# UWB_Tag.net
KiCad netlist of a schematic drawn in Altium Designer
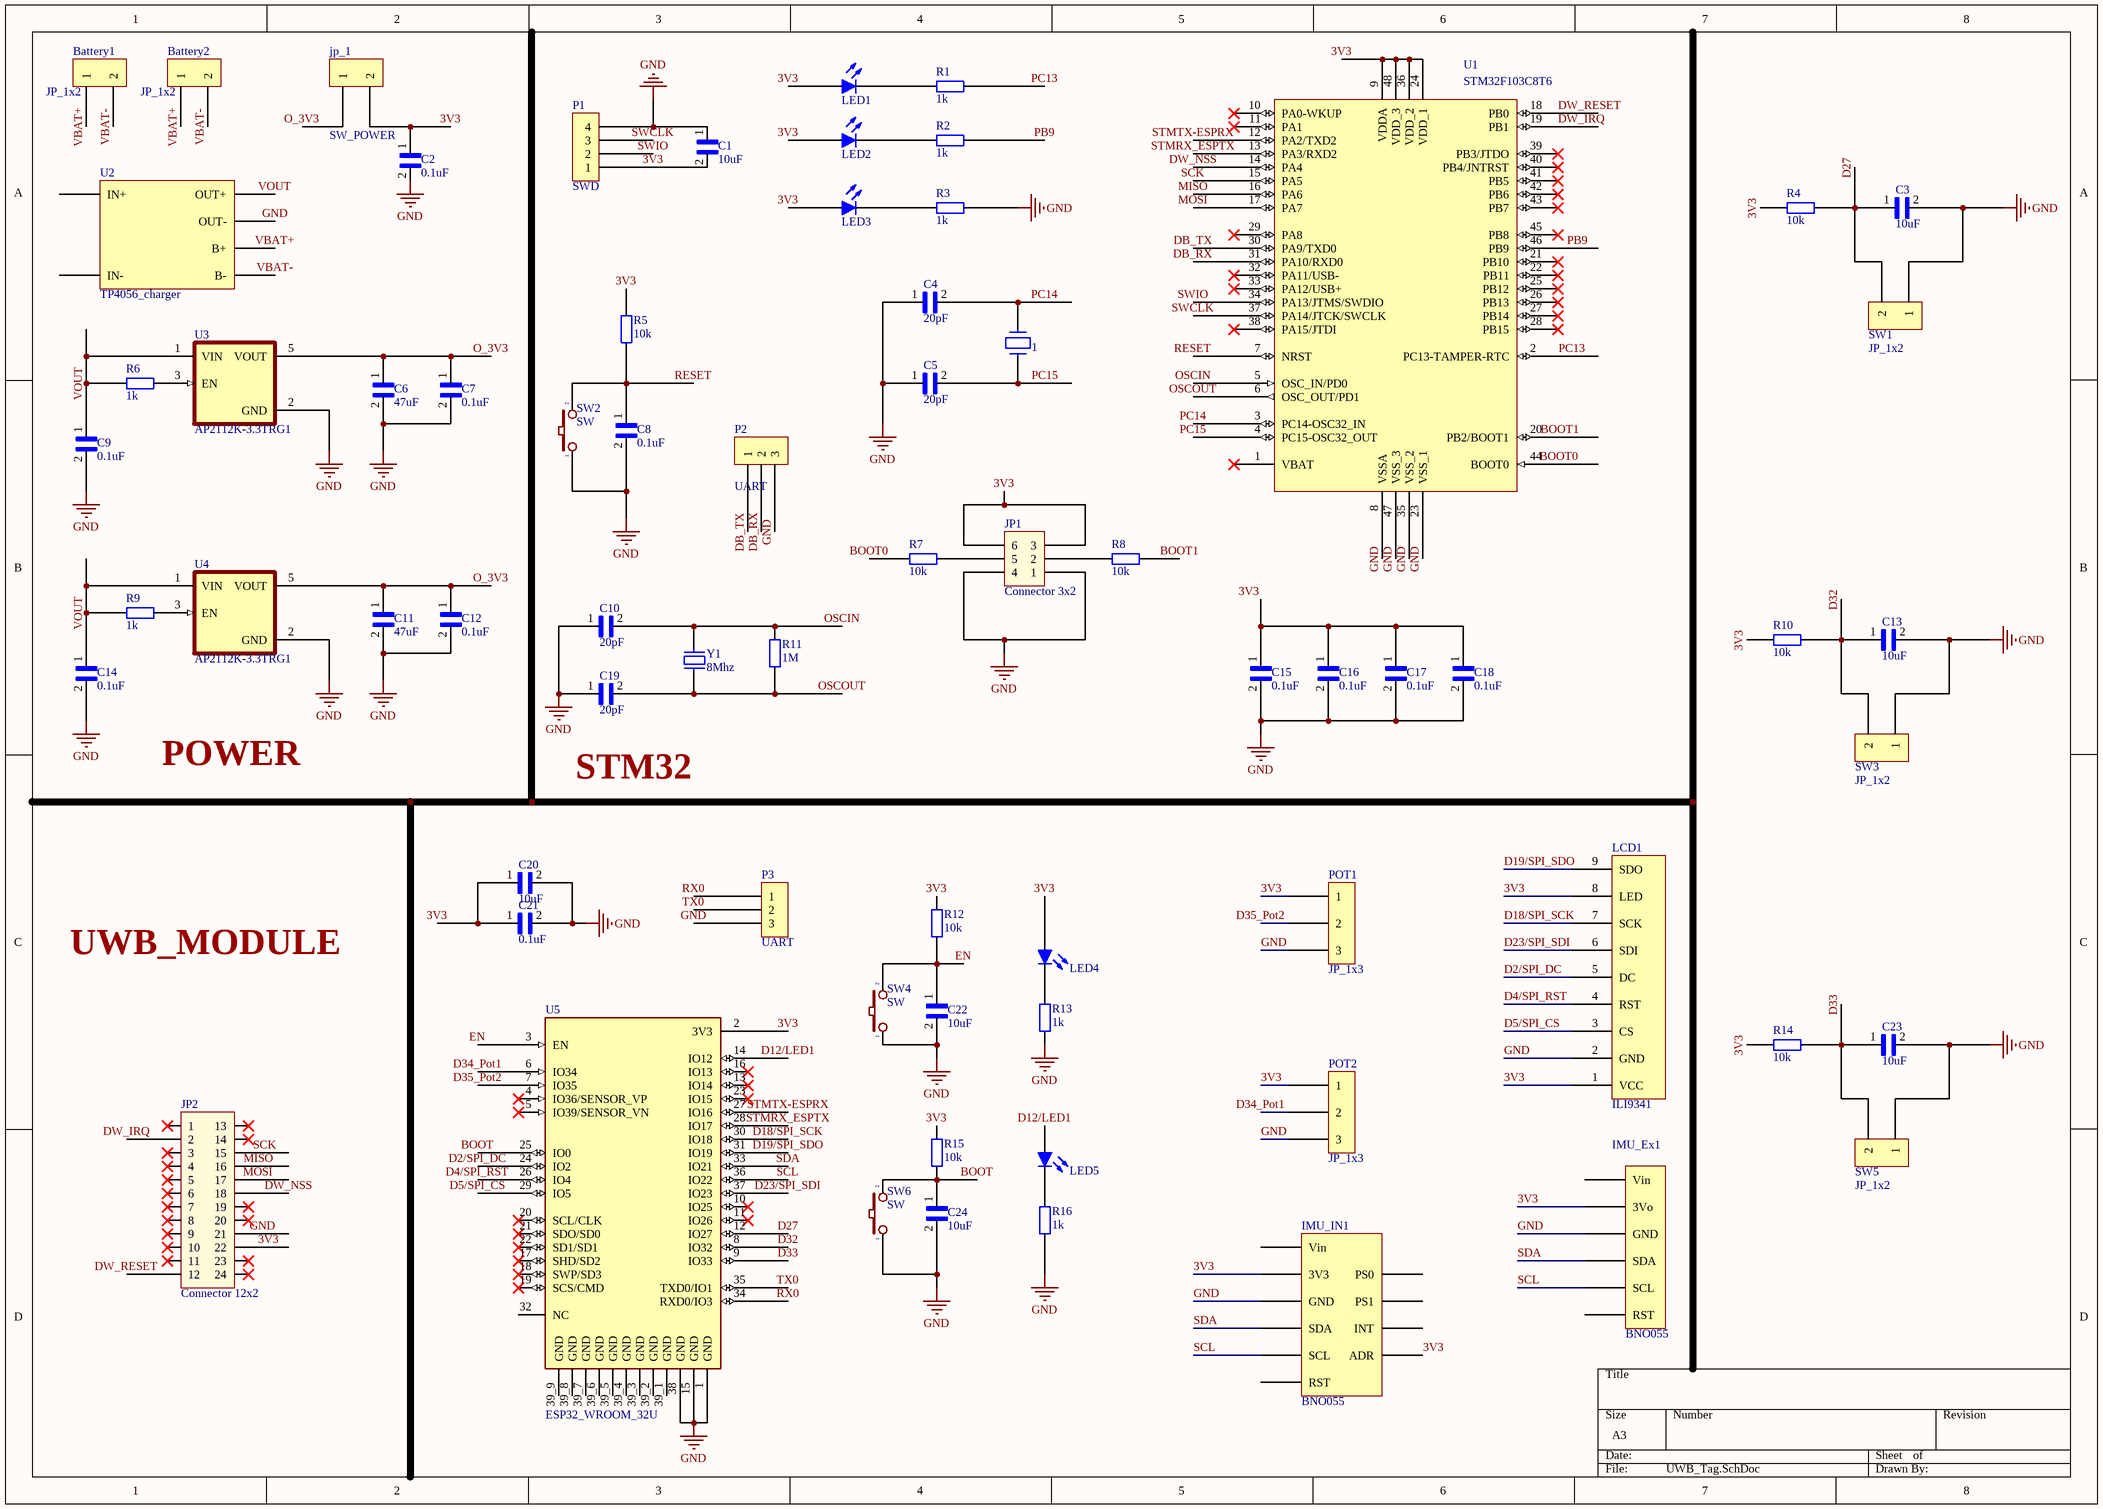
[diagram p0: UWB_Tag.SchDoc]

(export (version "E")
  (design (tool "Eeschema 10.0.6"))
  (components
    (comp (ref "1")
      (value "ABS07")
      (footprint "ABS07")
      (description "SMD Quartz Crystal")
      (fields (field (name "CREATED BY") "Zion Blue") (field (name "PUBLISHER") "Cynetik Group"))
      (libsource (lib "Cty1") (part "ABS07"))
    )
    (comp (ref "Battery1") (value "JP_1x2") (footprint "JP_1x2") (libsource (lib "") (part "JP_1x2_1")))
    (comp (ref "Battery2") (value "JP_1x2") (footprint "JP_1x2") (libsource (lib "") (part "JP_1x2_1")))
    (comp (ref "C1")
      (value "10uF")
      (footprint "Capacitor_0805")
      (description "Capacitor; Ceramic; Cap; .220uF; Tol 10%; SMT; Vol-Rtg 50V; X7R; Tape And Reel")
      (libsource (lib "") (part "Capacitor_0805_1"))
    )
    (comp (ref "C2")
      (value "0.1uF")
      (footprint "Capacitor_0805")
      (description "Capacitor; Ceramic; Cap; .220uF; Tol 10%; SMT; Vol-Rtg 50V; X7R; Tape And Reel")
      (libsource (lib "") (part "Capacitor_0805_1"))
    )
    (comp (ref "C3")
      (value "10uF")
      (footprint "Capacitor_0805")
      (description "Capacitor; Ceramic; Cap; .220uF; Tol 10%; SMT; Vol-Rtg 50V; X7R; Tape And Reel")
      (libsource (lib "Target_tracking_20242v3") (part "Capacitor_0805"))
    )
    (comp (ref "C4")
      (value "20pF")
      (footprint "Capacitor_0805")
      (description "Capacitor; Ceramic; Cap; .220uF; Tol 10%; SMT; Vol-Rtg 50V; X7R; Tape And Reel")
      (libsource (lib "Target_tracking_20242v3") (part "Capacitor_0805"))
    )
    (comp (ref "C5")
      (value "20pF")
      (footprint "Capacitor_0805")
      (description "Capacitor; Ceramic; Cap; .220uF; Tol 10%; SMT; Vol-Rtg 50V; X7R; Tape And Reel")
      (libsource (lib "Target_tracking_20242v3") (part "Capacitor_0805"))
    )
    (comp (ref "C6")
      (value "47uF")
      (footprint "Capacitor_0805")
      (description "Capacitor; Ceramic; Cap; .220uF; Tol 10%; SMT; Vol-Rtg 50V; X7R; Tape And Reel")
      (libsource (lib "") (part "Capacitor_0805_1"))
    )
    (comp (ref "C7")
      (value "0.1uF")
      (footprint "Capacitor_0805")
      (description "Capacitor; Ceramic; Cap; .220uF; Tol 10%; SMT; Vol-Rtg 50V; X7R; Tape And Reel")
      (libsource (lib "") (part "Capacitor_0805_1"))
    )
    (comp (ref "C8")
      (value "0.1uF")
      (footprint "Capacitor_0805")
      (description "Capacitor; Ceramic; Cap; .220uF; Tol 10%; SMT; Vol-Rtg 50V; X7R; Tape And Reel")
      (libsource (lib "") (part "Capacitor_0805_1"))
    )
    (comp (ref "C9")
      (value "0.1uF")
      (footprint "Capacitor_0805")
      (description "Capacitor; Ceramic; Cap; .220uF; Tol 10%; SMT; Vol-Rtg 50V; X7R; Tape And Reel")
      (libsource (lib "") (part "Capacitor_0805_1"))
    )
    (comp (ref "C10")
      (value "20pF")
      (footprint "Capacitor_0805")
      (description "Capacitor; Ceramic; Cap; .220uF; Tol 10%; SMT; Vol-Rtg 50V; X7R; Tape And Reel")
      (libsource (lib "Target_tracking_20242v3") (part "Capacitor_0805"))
    )
    (comp (ref "C11")
      (value "47uF")
      (footprint "Capacitor_0805")
      (description "Capacitor; Ceramic; Cap; .220uF; Tol 10%; SMT; Vol-Rtg 50V; X7R; Tape And Reel")
      (libsource (lib "") (part "Capacitor_0805_1"))
    )
    (comp (ref "C12")
      (value "0.1uF")
      (footprint "Capacitor_0805")
      (description "Capacitor; Ceramic; Cap; .220uF; Tol 10%; SMT; Vol-Rtg 50V; X7R; Tape And Reel")
      (libsource (lib "") (part "Capacitor_0805_1"))
    )
    (comp (ref "C13")
      (value "10uF")
      (footprint "Capacitor_0805")
      (description "Capacitor; Ceramic; Cap; .220uF; Tol 10%; SMT; Vol-Rtg 50V; X7R; Tape And Reel")
      (libsource (lib "Target_tracking_20242v3") (part "Capacitor_0805"))
    )
    (comp (ref "C14")
      (value "0.1uF")
      (footprint "Capacitor_0805")
      (description "Capacitor; Ceramic; Cap; .220uF; Tol 10%; SMT; Vol-Rtg 50V; X7R; Tape And Reel")
      (libsource (lib "") (part "Capacitor_0805_1"))
    )
    (comp (ref "C15")
      (value "0.1uF")
      (footprint "Capacitor_0805")
      (description "Capacitor; Ceramic; Cap; .220uF; Tol 10%; SMT; Vol-Rtg 50V; X7R; Tape And Reel")
      (libsource (lib "") (part "Capacitor_0805_1"))
    )
    (comp (ref "C16")
      (value "0.1uF")
      (footprint "Capacitor_0805")
      (description "Capacitor; Ceramic; Cap; .220uF; Tol 10%; SMT; Vol-Rtg 50V; X7R; Tape And Reel")
      (libsource (lib "") (part "Capacitor_0805_1"))
    )
    (comp (ref "C17")
      (value "0.1uF")
      (footprint "Capacitor_0805")
      (description "Capacitor; Ceramic; Cap; .220uF; Tol 10%; SMT; Vol-Rtg 50V; X7R; Tape And Reel")
      (libsource (lib "") (part "Capacitor_0805_1"))
    )
    (comp (ref "C18")
      (value "0.1uF")
      (footprint "Capacitor_0805")
      (description "Capacitor; Ceramic; Cap; .220uF; Tol 10%; SMT; Vol-Rtg 50V; X7R; Tape And Reel")
      (libsource (lib "") (part "Capacitor_0805_1"))
    )
    (comp (ref "C19")
      (value "20pF")
      (footprint "Capacitor_0805")
      (description "Capacitor; Ceramic; Cap; .220uF; Tol 10%; SMT; Vol-Rtg 50V; X7R; Tape And Reel")
      (libsource (lib "Target_tracking_20242v3") (part "Capacitor_0805"))
    )
    (comp (ref "C20")
      (value "10uF")
      (footprint "Capacitor_0805")
      (description "Capacitor; Ceramic; Cap; .220uF; Tol 10%; SMT; Vol-Rtg 50V; X7R; Tape And Reel")
      (libsource (lib "Target_tracking_20242v3") (part "Capacitor_0805"))
    )
    (comp (ref "C21")
      (value "0.1uF")
      (footprint "Capacitor_0805")
      (description "Capacitor; Ceramic; Cap; .220uF; Tol 10%; SMT; Vol-Rtg 50V; X7R; Tape And Reel")
      (libsource (lib "Target_tracking_20242v3") (part "Capacitor_0805"))
    )
    (comp (ref "C22")
      (value "10uF")
      (footprint "Capacitor_0805")
      (description "Capacitor; Ceramic; Cap; .220uF; Tol 10%; SMT; Vol-Rtg 50V; X7R; Tape And Reel")
      (libsource (lib "") (part "Capacitor_0805_1"))
    )
    (comp (ref "C23")
      (value "10uF")
      (footprint "Capacitor_0805")
      (description "Capacitor; Ceramic; Cap; .220uF; Tol 10%; SMT; Vol-Rtg 50V; X7R; Tape And Reel")
      (libsource (lib "Target_tracking_20242v3") (part "Capacitor_0805"))
    )
    (comp (ref "C24")
      (value "10uF")
      (footprint "Capacitor_0805")
      (description "Capacitor; Ceramic; Cap; .220uF; Tol 10%; SMT; Vol-Rtg 50V; X7R; Tape And Reel")
      (libsource (lib "") (part "Capacitor_0805_1"))
    )
    (comp (ref "IMU_Ex1")
      (value "BNO055")
      (footprint "BNO055_External")
      (libsource (lib "Target_tracking_20242v2") (part "BNO055_External"))
    )
    (comp (ref "IMU_IN1")
      (value "BNO055")
      (footprint "BNO055_Internal")
      (libsource (lib "Target_tracking_20242v3") (part "BNO055"))
    )
    (comp (ref "JP1") (value "Connector 3x2") (footprint "JP3x2") (libsource (lib "Cty1") (part "JP3x2")))
    (comp (ref "JP2")
      (value "Connector 12x2")
      (footprint "JP12X2_1")
      (libsource (lib "Cty1") (part "JP12x2"))
    )
    (comp (ref "jp_1")
      (value "SW_POWER")
      (footprint "JP_1x2")
      (libsource (lib "Target_tracking_20242v3") (part "JP_1x2"))
    )
    (comp (ref "LCD1")
      (value "ILI9341")
      (footprint "ILI9341_LCD3.5")
      (libsource (lib "Target_tracking_20242v2") (part "ILI9341_LCD3.5"))
    )
    (comp (ref "LED1")
      (value "Led")
      (footprint "Led 0805 Blue")
      (description "Typical LED")
      (libsource (lib "Project_LoRa") (part "Led"))
    )
    (comp (ref "LED2")
      (value "Led")
      (footprint "Led 0805 Blue")
      (description "Typical LED")
      (libsource (lib "Project_LoRa") (part "Led"))
    )
    (comp (ref "LED3")
      (value "Led")
      (footprint "Led 0805 Blue")
      (description "Typical LED")
      (libsource (lib "Project_LoRa") (part "Led"))
    )
    (comp (ref "LED4")
      (value "Led")
      (footprint "Led 0805 Blue")
      (description "Typical LED")
      (libsource (lib "Project_LoRa") (part "Led"))
    )
    (comp (ref "LED5")
      (value "Led")
      (footprint "Led 0805 Blue")
      (description "Typical LED")
      (libsource (lib "Project_LoRa") (part "Led"))
    )
    (comp (ref "P1")
      (value "SWD")
      (footprint "HDR/Header/4/BOX")
      (description "Header, 4-Pin")
      (libsource (lib "Project_LoRa") (part "Header 4_1"))
    )
    (comp (ref "P2")
      (value "UART")
      (footprint "HDR/Header/3/BOX")
      (description "Header, 3-Pin")
      (libsource (lib "Project_LoRa") (part "Header 3"))
    )
    (comp (ref "P3")
      (value "UART")
      (footprint "HDR/Header/3/BOX")
      (description "Header, 3-Pin")
      (libsource (lib "") (part "Header 3_1"))
    )
    (comp (ref "POT1")
      (value "JP_1x3")
      (footprint "JP_1x3")
      (libsource (lib "Target_tracking_20242v2") (part "JP_1x3"))
    )
    (comp (ref "POT2")
      (value "JP_1x3")
      (footprint "JP_1x3")
      (libsource (lib "Target_tracking_20242v2") (part "JP_1x3"))
    )
    (comp (ref "R1")
      (value "1k")
      (footprint "tro smd 0805")
      (description "Dán")
      (libsource (lib "Project_LoRa") (part "Tro 0805 1% 1k"))
    )
    (comp (ref "R2")
      (value "1k")
      (footprint "tro smd 0805")
      (description "Dán")
      (libsource (lib "Project_LoRa") (part "Tro 0805 1% 1k"))
    )
    (comp (ref "R3")
      (value "1k")
      (footprint "tro smd 0805")
      (description "Dán")
      (libsource (lib "Project_LoRa") (part "Tro 0805 1% 1k"))
    )
    (comp (ref "R4")
      (value "10k")
      (footprint "tro smd 0805")
      (description "Dán")
      (libsource (lib "Project_LoRa") (part "Tro 0805 1% 10k"))
    )
    (comp (ref "R5")
      (value "10k")
      (footprint "tro smd 0805")
      (description "Dán")
      (libsource (lib "Project_LoRa") (part "Tro 0805 1% 10k"))
    )
    (comp (ref "R6")
      (value "1k")
      (footprint "tro smd 0805")
      (description "Dán")
      (libsource (lib "Project_LoRa") (part "Tro 0805 1% 1k"))
    )
    (comp (ref "R7")
      (value "10k")
      (footprint "tro smd 0805")
      (description "Dán")
      (libsource (lib "Project_LoRa") (part "Tro 0805 1% 10k"))
    )
    (comp (ref "R8")
      (value "10k")
      (footprint "tro smd 0805")
      (description "Dán")
      (libsource (lib "Project_LoRa") (part "Tro 0805 1% 10k"))
    )
    (comp (ref "R9")
      (value "1k")
      (footprint "tro smd 0805")
      (description "Dán")
      (libsource (lib "Project_LoRa") (part "Tro 0805 1% 1k"))
    )
    (comp (ref "R10")
      (value "10k")
      (footprint "tro smd 0805")
      (description "Dán")
      (libsource (lib "Project_LoRa") (part "Tro 0805 1% 10k"))
    )
    (comp (ref "R11")
      (value "1M")
      (footprint "tro smd 0805")
      (description "Dán")
      (libsource (lib "Project_LoRa") (part "Tro 0805 1% 1M"))
    )
    (comp (ref "R12")
      (value "10k")
      (footprint "tro smd 0805")
      (description "Dán")
      (libsource (lib "Project_LoRa") (part "Tro 0805 1% 10k"))
    )
    (comp (ref "R13")
      (value "1k")
      (footprint "tro smd 0805")
      (description "Dán")
      (libsource (lib "Project_LoRa") (part "Tro 0805 1% 1k"))
    )
    (comp (ref "R14")
      (value "10k")
      (footprint "tro smd 0805")
      (description "Dán")
      (libsource (lib "Project_LoRa") (part "Tro 0805 1% 10k"))
    )
    (comp (ref "R15")
      (value "10k")
      (footprint "tro smd 0805")
      (description "Dán")
      (libsource (lib "Project_LoRa") (part "Tro 0805 1% 10k"))
    )
    (comp (ref "R16")
      (value "1k")
      (footprint "tro smd 0805")
      (description "Dán")
      (libsource (lib "Project_LoRa") (part "Tro 0805 1% 1k"))
    )
    (comp (ref "SW1")
      (value "JP_1x2")
      (footprint "JP_1x2")
      (libsource (lib "Target_tracking_20242v2") (part "JP_1x2"))
    )
    (comp (ref "SW2")
      (value "SW")
      (footprint "SW1-SMD")
      (description "Switch button 2 pin")
      (libsource (lib "Project_LoRa") (part "SW2"))
    )
    (comp (ref "SW3")
      (value "JP_1x2")
      (footprint "JP_1x2")
      (libsource (lib "Target_tracking_20242v2") (part "JP_1x2"))
    )
    (comp (ref "SW4")
      (value "SW")
      (footprint "SW1-SMD")
      (description "Switch button 2 pin")
      (libsource (lib "Project_LoRa") (part "SW2"))
    )
    (comp (ref "SW5")
      (value "JP_1x2")
      (footprint "JP_1x2")
      (libsource (lib "Target_tracking_20242v2") (part "JP_1x2"))
    )
    (comp (ref "SW6")
      (value "SW")
      (footprint "SW1-SMD")
      (description "Switch button 2 pin")
      (libsource (lib "Project_LoRa") (part "SW2"))
    )
    (comp (ref "U1")
      (value "STM32F103C8T6")
      (footprint "LQFP48")
      (fields (field (name "PUBLISHER") "Altium Limited"))
      (libsource (lib "Project_LoRa") (part "STM32F103C8T6"))
    )
    (comp (ref "U2")
      (value "TP4056_charger")
      (footprint "TP4056_charger")
      (libsource (lib "Target_tracking_20242v3") (part "TP4056_charger"))
    )
    (comp (ref "U3")
      (value "AP2112K-3.3TRG1")
      (footprint "SOT95P285X140-5N")
      (description "Linear Voltage Regulator IC Positive Fixed 1 Output 600mA SOT-25")
      (fields (field (name "MF") "Diodes Inc."))
      (libsource (lib "Project_LoRa") (part "AP2112K-3.3TRG1"))
    )
    (comp (ref "U4")
      (value "AP2112K-3.3TRG1")
      (footprint "SOT95P285X140-5N")
      (description "Linear Voltage Regulator IC Positive Fixed 1 Output 600mA SOT-25")
      (fields (field (name "MF") "Diodes Inc."))
      (libsource (lib "Project_LoRa") (part "AP2112K-3.3TRG1"))
    )
    (comp (ref "U5")
      (value "ESP32_WROOM_32U")
      (footprint "ESP32_WROOM_32U")
      (libsource (lib "Target_tracking_20242v3") (part "ESP32_WROOM_32U"))
    )
    (comp (ref "Y1")
      (value "8Mhz")
      (footprint "Thach Anh 2 chan SMD5032")
      (description "Crystal For all Crystal 2pin.")
      (libsource (lib "Project_LoRa") (part "Thach Anh 2 chan SMD 5032"))
    )
  )
  (nets
    (net (code "1") (name "/3V3") (class "Default")
      (node (ref "C1") (pin "2") (pinfunction "2_2") (pintype "passive"))
      (node (ref "C15") (pin "1") (pinfunction "1_1") (pintype "passive"))
      (node (ref "C16") (pin "1") (pinfunction "1_1") (pintype "passive"))
      (node (ref "C17") (pin "1") (pinfunction "1_1") (pintype "passive"))
      (node (ref "C18") (pin "1") (pinfunction "1_1") (pintype "passive"))
      (node (ref "C2") (pin "1") (pinfunction "1_1") (pintype "passive"))
      (node (ref "C20") (pin "1") (pinfunction "1_1") (pintype "passive"))
      (node (ref "C21") (pin "1") (pinfunction "1_1") (pintype "passive"))
      (node (ref "IMU_Ex1") (pin "2") (pinfunction "3Vo_2") (pintype "passive"))
      (node (ref "IMU_IN1") (pin "2") (pinfunction "3V3_2") (pintype "passive"))
      (node (ref "IMU_IN1") (pin "7") (pinfunction "ADR_7") (pintype "passive"))
      (node (ref "JP1") (pin "3") (pinfunction "3_3") (pintype "passive"))
      (node (ref "JP1") (pin "6") (pinfunction "6_6") (pintype "passive"))
      (node (ref "JP2") (pin "22") (pinfunction "22_22") (pintype "passive"))
      (node (ref "LCD1") (pin "1") (pinfunction "VCC_1") (pintype "passive"))
      (node (ref "LCD1") (pin "8") (pinfunction "LED_8") (pintype "passive"))
      (node (ref "LED1") (pin "1") (pinfunction "A_1") (pintype "passive"))
      (node (ref "LED2") (pin "1") (pinfunction "A_1") (pintype "passive"))
      (node (ref "LED3") (pin "1") (pinfunction "A_1") (pintype "passive"))
      (node (ref "LED4") (pin "1") (pinfunction "A_1") (pintype "passive"))
      (node (ref "P1") (pin "1") (pinfunction "1_1") (pintype "passive"))
      (node (ref "POT1") (pin "1") (pinfunction "1_1") (pintype "passive"))
      (node (ref "POT2") (pin "1") (pinfunction "1_1") (pintype "passive"))
      (node (ref "R10") (pin "2") (pinfunction "2_2") (pintype "passive"))
      (node (ref "R12") (pin "2") (pinfunction "2_2") (pintype "passive"))
      (node (ref "R14") (pin "2") (pinfunction "2_2") (pintype "passive"))
      (node (ref "R15") (pin "2") (pinfunction "2_2") (pintype "passive"))
      (node (ref "R4") (pin "2") (pinfunction "2_2") (pintype "passive"))
      (node (ref "R5") (pin "2") (pinfunction "2_2") (pintype "passive"))
      (node (ref "U1") (pin "24") (pinfunction "VDD_1_24") (pintype "power_in"))
      (node (ref "U1") (pin "36") (pinfunction "VDD_2_36") (pintype "power_in"))
      (node (ref "U1") (pin "48") (pinfunction "VDD_3_48") (pintype "power_in"))
      (node (ref "U1") (pin "9") (pinfunction "VDDA_9") (pintype "power_in"))
      (node (ref "U5") (pin "2") (pinfunction "3V3_2") (pintype "power_in"))
      (node (ref "jp_1") (pin "2") (pinfunction "2_2") (pintype "passive"))
    )
    (net (code "2") (name "/BOOT") (class "Default")
      (node (ref "C24") (pin "1") (pinfunction "1_1") (pintype "passive"))
      (node (ref "R15") (pin "1") (pinfunction "1_1") (pintype "passive"))
      (node (ref "SW6") (pin "2") (pinfunction "2_2") (pintype "passive"))
      (node (ref "U5") (pin "25") (pinfunction "IO0_25") (pintype "bidirectional"))
    )
    (net (code "3") (name "/BOOT0") (class "Default")
      (node (ref "R7") (pin "1") (pinfunction "1_1") (pintype "passive"))
      (node (ref "U1") (pin "44") (pinfunction "BOOT0_44") (pintype "input"))
    )
    (net (code "4") (name "/BOOT1") (class "Default")
      (node (ref "R8") (pin "2") (pinfunction "2_2") (pintype "passive"))
      (node (ref "U1") (pin "20") (pinfunction "PB2/BOOT1_20") (pintype "bidirectional"))
    )
    (net (code "5") (name "/D2{slash}SPI_DC") (class "Default")
      (node (ref "LCD1") (pin "5") (pinfunction "DC_5") (pintype "passive"))
      (node (ref "U5") (pin "24") (pinfunction "IO2_24") (pintype "bidirectional"))
    )
    (net (code "6") (name "/D4{slash}SPI_RST") (class "Default")
      (node (ref "LCD1") (pin "4") (pinfunction "RST_4") (pintype "passive"))
      (node (ref "U5") (pin "26") (pinfunction "IO4_26") (pintype "bidirectional"))
    )
    (net (code "7") (name "/D5{slash}SPI_CS") (class "Default")
      (node (ref "LCD1") (pin "3") (pinfunction "CS_3") (pintype "passive"))
      (node (ref "U5") (pin "29") (pinfunction "IO5_29") (pintype "bidirectional"))
    )
    (net (code "8") (name "/D12{slash}LED1") (class "Default")
      (node (ref "LED5") (pin "1") (pinfunction "A_1") (pintype "passive"))
      (node (ref "U5") (pin "14") (pinfunction "IO12_14") (pintype "bidirectional"))
    )
    (net (code "9") (name "/D18{slash}SPI_SCK") (class "Default")
      (node (ref "LCD1") (pin "7") (pinfunction "SCK_7") (pintype "passive"))
      (node (ref "U5") (pin "30") (pinfunction "IO18_30") (pintype "bidirectional"))
    )
    (net (code "10") (name "/D19{slash}SPI_SDO") (class "Default")
      (node (ref "LCD1") (pin "9") (pinfunction "SDO_9") (pintype "passive"))
      (node (ref "U5") (pin "31") (pinfunction "IO19_31") (pintype "bidirectional"))
    )
    (net (code "11") (name "/D23{slash}SPI_SDI") (class "Default")
      (node (ref "LCD1") (pin "6") (pinfunction "SDI_6") (pintype "passive"))
      (node (ref "U5") (pin "37") (pinfunction "IO23_37") (pintype "bidirectional"))
    )
    (net (code "12") (name "/D27") (class "Default")
      (node (ref "C3") (pin "1") (pinfunction "1_1") (pintype "passive"))
      (node (ref "R4") (pin "1") (pinfunction "1_1") (pintype "passive"))
      (node (ref "SW1") (pin "2") (pinfunction "2_2") (pintype "passive"))
      (node (ref "U5") (pin "12") (pinfunction "IO27_12") (pintype "bidirectional"))
    )
    (net (code "13") (name "/D32") (class "Default")
      (node (ref "C13") (pin "1") (pinfunction "1_1") (pintype "passive"))
      (node (ref "R10") (pin "1") (pinfunction "1_1") (pintype "passive"))
      (node (ref "SW3") (pin "2") (pinfunction "2_2") (pintype "passive"))
      (node (ref "U5") (pin "8") (pinfunction "IO32_8") (pintype "bidirectional"))
    )
    (net (code "14") (name "/D33") (class "Default")
      (node (ref "C23") (pin "1") (pinfunction "1_1") (pintype "passive"))
      (node (ref "R14") (pin "1") (pinfunction "1_1") (pintype "passive"))
      (node (ref "SW5") (pin "2") (pinfunction "2_2") (pintype "passive"))
      (node (ref "U5") (pin "9") (pinfunction "IO33_9") (pintype "bidirectional"))
    )
    (net (code "15") (name "/D34_Pot1") (class "Default")
      (node (ref "POT2") (pin "2") (pinfunction "2_2") (pintype "passive"))
      (node (ref "U5") (pin "6") (pinfunction "IO34_6") (pintype "input"))
    )
    (net (code "16") (name "/D35_Pot2") (class "Default")
      (node (ref "POT1") (pin "2") (pinfunction "2_2") (pintype "passive"))
      (node (ref "U5") (pin "7") (pinfunction "IO35_7") (pintype "input"))
    )
    (net (code "17") (name "/DB_RX") (class "Default")
      (node (ref "P2") (pin "2") (pinfunction "2_2") (pintype "passive"))
      (node (ref "U1") (pin "31") (pinfunction "PA10/RXD0_31") (pintype "bidirectional"))
    )
    (net (code "18") (name "/DB_TX") (class "Default")
      (node (ref "P2") (pin "1") (pinfunction "1_1") (pintype "passive"))
      (node (ref "U1") (pin "30") (pinfunction "PA9/TXD0_30") (pintype "bidirectional"))
    )
    (net (code "19") (name "/DW_IRQ") (class "Default")
      (node (ref "JP2") (pin "2") (pinfunction "2_2") (pintype "passive"))
      (node (ref "U1") (pin "19") (pinfunction "PB1_19") (pintype "bidirectional"))
    )
    (net (code "20") (name "/DW_NSS") (class "Default")
      (node (ref "JP2") (pin "18") (pinfunction "18_18") (pintype "passive"))
      (node (ref "U1") (pin "14") (pinfunction "PA4_14") (pintype "bidirectional"))
    )
    (net (code "21") (name "/DW_RESET") (class "Default")
      (node (ref "JP2") (pin "12") (pinfunction "12_12") (pintype "passive"))
      (node (ref "U1") (pin "18") (pinfunction "PB0_18") (pintype "bidirectional"))
    )
    (net (code "22") (name "/EN") (class "Default")
      (node (ref "C22") (pin "1") (pinfunction "1_1") (pintype "passive"))
      (node (ref "R12") (pin "1") (pinfunction "1_1") (pintype "passive"))
      (node (ref "SW4") (pin "2") (pinfunction "2_2") (pintype "passive"))
      (node (ref "U5") (pin "3") (pinfunction "EN_3") (pintype "input"))
    )
    (net (code "23") (name "/MISO") (class "Default")
      (node (ref "JP2") (pin "16") (pinfunction "16_16") (pintype "passive"))
      (node (ref "U1") (pin "16") (pinfunction "PA6_16") (pintype "bidirectional"))
    )
    (net (code "24") (name "/MOSI") (class "Default")
      (node (ref "JP2") (pin "17") (pinfunction "17_17") (pintype "passive"))
      (node (ref "U1") (pin "17") (pinfunction "PA7_17") (pintype "bidirectional"))
    )
    (net (code "25") (name "/OSCIN") (class "Default")
      (node (ref "C10") (pin "2") (pinfunction "2_2") (pintype "passive"))
      (node (ref "R11") (pin "2") (pinfunction "2_2") (pintype "passive"))
      (node (ref "U1") (pin "5") (pinfunction "OSC_IN/PD0_5") (pintype "input"))
      (node (ref "Y1") (pin "2") (pinfunction "2_2") (pintype "passive"))
    )
    (net (code "26") (name "/OSCOUT") (class "Default")
      (node (ref "C19") (pin "2") (pinfunction "2_2") (pintype "passive"))
      (node (ref "R11") (pin "1") (pinfunction "1_1") (pintype "passive"))
      (node (ref "U1") (pin "6") (pinfunction "OSC_OUT/PD1_6") (pintype "output"))
      (node (ref "Y1") (pin "1") (pinfunction "1_1") (pintype "passive"))
    )
    (net (code "27") (name "/O_3V3") (class "Default")
      (node (ref "C11") (pin "1") (pinfunction "1_1") (pintype "passive"))
      (node (ref "C12") (pin "1") (pinfunction "1_1") (pintype "passive"))
      (node (ref "C6") (pin "1") (pinfunction "1_1") (pintype "passive"))
      (node (ref "C7") (pin "1") (pinfunction "1_1") (pintype "passive"))
      (node (ref "U3") (pin "5") (pinfunction "VOUT_5") (pintype "power_in"))
      (node (ref "U4") (pin "5") (pinfunction "VOUT_5") (pintype "power_in"))
      (node (ref "jp_1") (pin "1") (pinfunction "1_1") (pintype "passive"))
    )
    (net (code "28") (name "/PB9") (class "Default")
      (node (ref "R2") (pin "2") (pinfunction "2_2") (pintype "passive"))
      (node (ref "U1") (pin "46") (pinfunction "PB9_46") (pintype "bidirectional"))
    )
    (net (code "29") (name "/PC13") (class "Default")
      (node (ref "R1") (pin "2") (pinfunction "2_2") (pintype "passive"))
      (node (ref "U1") (pin "2") (pinfunction "PC13-TAMPER-RTC_2") (pintype "bidirectional"))
    )
    (net (code "30") (name "/PC14") (class "Default")
      (node (ref "1") (pin "2") (pinfunction "2_2") (pintype "passive"))
      (node (ref "C4") (pin "2") (pinfunction "2_2") (pintype "passive"))
      (node (ref "U1") (pin "3") (pinfunction "PC14-OSC32_IN_3") (pintype "bidirectional"))
    )
    (net (code "31") (name "/PC15") (class "Default")
      (node (ref "1") (pin "1") (pinfunction "1_1") (pintype "passive"))
      (node (ref "C5") (pin "2") (pinfunction "2_2") (pintype "passive"))
      (node (ref "U1") (pin "4") (pinfunction "PC15-OSC32_OUT_4") (pintype "bidirectional"))
    )
    (net (code "32") (name "/RESET") (class "Default")
      (node (ref "C8") (pin "1") (pinfunction "1_1") (pintype "passive"))
      (node (ref "R5") (pin "1") (pinfunction "1_1") (pintype "passive"))
      (node (ref "SW2") (pin "2") (pinfunction "2_2") (pintype "passive"))
      (node (ref "U1") (pin "7") (pinfunction "NRST_7") (pintype "bidirectional"))
    )
    (net (code "33") (name "/RX0") (class "Default")
      (node (ref "P3") (pin "1") (pinfunction "1_1") (pintype "passive"))
      (node (ref "U5") (pin "34") (pinfunction "RXD0/IO3_34") (pintype "bidirectional"))
    )
    (net (code "34") (name "/SCK") (class "Default")
      (node (ref "JP2") (pin "15") (pinfunction "15_15") (pintype "passive"))
      (node (ref "U1") (pin "15") (pinfunction "PA5_15") (pintype "bidirectional"))
    )
    (net (code "35") (name "/SCL") (class "Default")
      (node (ref "IMU_Ex1") (pin "5") (pinfunction "SCL_5") (pintype "passive"))
      (node (ref "IMU_IN1") (pin "5") (pinfunction "SCL_5") (pintype "passive"))
      (node (ref "U5") (pin "36") (pinfunction "IO22_36") (pintype "bidirectional"))
    )
    (net (code "36") (name "/SDA") (class "Default")
      (node (ref "IMU_Ex1") (pin "4") (pinfunction "SDA_4") (pintype "passive"))
      (node (ref "IMU_IN1") (pin "4") (pinfunction "SDA_4") (pintype "passive"))
      (node (ref "U5") (pin "33") (pinfunction "IO21_33") (pintype "bidirectional"))
    )
    (net (code "37") (name "/STMRX_ESPTX") (class "Default")
      (node (ref "U1") (pin "13") (pinfunction "PA3/RXD2_13") (pintype "bidirectional"))
      (node (ref "U5") (pin "28") (pinfunction "IO17_28") (pintype "bidirectional"))
    )
    (net (code "38") (name "/STMTX-ESPRX") (class "Default")
      (node (ref "U1") (pin "12") (pinfunction "PA2/TXD2_12") (pintype "bidirectional"))
      (node (ref "U5") (pin "27") (pinfunction "IO16_27") (pintype "bidirectional"))
    )
    (net (code "39") (name "/SWCLK") (class "Default")
      (node (ref "P1") (pin "3") (pinfunction "3_3") (pintype "passive"))
      (node (ref "U1") (pin "37") (pinfunction "PA14/JTCK/SWCLK_37") (pintype "bidirectional"))
    )
    (net (code "40") (name "/SWIO") (class "Default")
      (node (ref "P1") (pin "2") (pinfunction "2_2") (pintype "passive"))
      (node (ref "U1") (pin "34") (pinfunction "PA13/JTMS/SWDIO_34") (pintype "bidirectional"))
    )
    (net (code "41") (name "/TX0") (class "Default")
      (node (ref "P3") (pin "2") (pinfunction "2_2") (pintype "passive"))
      (node (ref "U5") (pin "35") (pinfunction "TXD0/IO1_35") (pintype "bidirectional"))
    )
    (net (code "42") (name "/VBAT+") (class "Default")
      (node (ref "Battery1") (pin "1") (pinfunction "1_1") (pintype "passive"))
      (node (ref "Battery2") (pin "1") (pinfunction "1_1") (pintype "passive"))
      (node (ref "U2") (pin "1") (pinfunction "B+_1") (pintype "passive"))
    )
    (net (code "43") (name "/VBAT-") (class "Default")
      (node (ref "Battery1") (pin "2") (pinfunction "2_2") (pintype "passive"))
      (node (ref "Battery2") (pin "2") (pinfunction "2_2") (pintype "passive"))
      (node (ref "U2") (pin "2") (pinfunction "B-_2") (pintype "passive"))
    )
    (net (code "44") (name "/VOUT") (class "Default")
      (node (ref "C14") (pin "1") (pinfunction "1_1") (pintype "passive"))
      (node (ref "C9") (pin "1") (pinfunction "1_1") (pintype "passive"))
      (node (ref "R6") (pin "1") (pinfunction "1_1") (pintype "passive"))
      (node (ref "R9") (pin "1") (pinfunction "1_1") (pintype "passive"))
      (node (ref "U2") (pin "3") (pinfunction "OUT+_3") (pintype "passive"))
      (node (ref "U3") (pin "1") (pinfunction "VIN_1") (pintype "power_in"))
      (node (ref "U4") (pin "1") (pinfunction "VIN_1") (pintype "power_in"))
    )
    (net (code "45") (name "GND") (class "Default")
      (node (ref "C1") (pin "1") (pinfunction "1_1") (pintype "passive"))
      (node (ref "C10") (pin "1") (pinfunction "1_1") (pintype "passive"))
      (node (ref "C11") (pin "2") (pinfunction "2_2") (pintype "passive"))
      (node (ref "C12") (pin "2") (pinfunction "2_2") (pintype "passive"))
      (node (ref "C13") (pin "2") (pinfunction "2_2") (pintype "passive"))
      (node (ref "C14") (pin "2") (pinfunction "2_2") (pintype "passive"))
      (node (ref "C15") (pin "2") (pinfunction "2_2") (pintype "passive"))
      (node (ref "C16") (pin "2") (pinfunction "2_2") (pintype "passive"))
      (node (ref "C17") (pin "2") (pinfunction "2_2") (pintype "passive"))
      (node (ref "C18") (pin "2") (pinfunction "2_2") (pintype "passive"))
      (node (ref "C19") (pin "1") (pinfunction "1_1") (pintype "passive"))
      (node (ref "C2") (pin "2") (pinfunction "2_2") (pintype "passive"))
      (node (ref "C20") (pin "2") (pinfunction "2_2") (pintype "passive"))
      (node (ref "C21") (pin "2") (pinfunction "2_2") (pintype "passive"))
      (node (ref "C22") (pin "2") (pinfunction "2_2") (pintype "passive"))
      (node (ref "C23") (pin "2") (pinfunction "2_2") (pintype "passive"))
      (node (ref "C24") (pin "2") (pinfunction "2_2") (pintype "passive"))
      (node (ref "C3") (pin "2") (pinfunction "2_2") (pintype "passive"))
      (node (ref "C4") (pin "1") (pinfunction "1_1") (pintype "passive"))
      (node (ref "C5") (pin "1") (pinfunction "1_1") (pintype "passive"))
      (node (ref "C6") (pin "2") (pinfunction "2_2") (pintype "passive"))
      (node (ref "C7") (pin "2") (pinfunction "2_2") (pintype "passive"))
      (node (ref "C8") (pin "2") (pinfunction "2_2") (pintype "passive"))
      (node (ref "C9") (pin "2") (pinfunction "2_2") (pintype "passive"))
      (node (ref "IMU_Ex1") (pin "3") (pinfunction "GND_3") (pintype "passive"))
      (node (ref "IMU_IN1") (pin "3") (pinfunction "GND_3") (pintype "passive"))
      (node (ref "JP1") (pin "1") (pinfunction "1_1") (pintype "passive"))
      (node (ref "JP1") (pin "4") (pinfunction "4_4") (pintype "passive"))
      (node (ref "JP2") (pin "21") (pinfunction "21_21") (pintype "passive"))
      (node (ref "LCD1") (pin "2") (pinfunction "GND_2") (pintype "passive"))
      (node (ref "P1") (pin "4") (pinfunction "4_4") (pintype "passive"))
      (node (ref "P2") (pin "3") (pinfunction "3_3") (pintype "passive"))
      (node (ref "P3") (pin "3") (pinfunction "3_3") (pintype "passive"))
      (node (ref "POT1") (pin "3") (pinfunction "3_3") (pintype "passive"))
      (node (ref "POT2") (pin "3") (pinfunction "3_3") (pintype "passive"))
      (node (ref "R13") (pin "2") (pinfunction "2_2") (pintype "passive"))
      (node (ref "R16") (pin "2") (pinfunction "2_2") (pintype "passive"))
      (node (ref "R3") (pin "2") (pinfunction "2_2") (pintype "passive"))
      (node (ref "SW1") (pin "1") (pinfunction "1_1") (pintype "passive"))
      (node (ref "SW2") (pin "1") (pinfunction "1_1") (pintype "passive"))
      (node (ref "SW3") (pin "1") (pinfunction "1_1") (pintype "passive"))
      (node (ref "SW4") (pin "1") (pinfunction "1_1") (pintype "passive"))
      (node (ref "SW5") (pin "1") (pinfunction "1_1") (pintype "passive"))
      (node (ref "SW6") (pin "1") (pinfunction "1_1") (pintype "passive"))
      (node (ref "U1") (pin "23") (pinfunction "VSS_1_23") (pintype "power_in"))
      (node (ref "U1") (pin "35") (pinfunction "VSS_2_35") (pintype "power_in"))
      (node (ref "U1") (pin "47") (pinfunction "VSS_3_47") (pintype "power_in"))
      (node (ref "U1") (pin "8") (pinfunction "VSSA_8") (pintype "power_in"))
      (node (ref "U2") (pin "4") (pinfunction "OUT-_4") (pintype "passive"))
      (node (ref "U3") (pin "2") (pinfunction "GND_2") (pintype "power_in"))
      (node (ref "U4") (pin "2") (pinfunction "GND_2") (pintype "power_in"))
      (node (ref "U5") (pin "1") (pinfunction "GND_1") (pintype "power_in"))
      (node (ref "U5") (pin "15") (pinfunction "GND_15") (pintype "power_in"))
      (node (ref "U5") (pin "38") (pinfunction "GND_38") (pintype "power_in"))
    )
    (net (code "46") (name "Net-(JP1-Pad2)") (class "Default")
      (node (ref "JP1") (pin "2") (pinfunction "2_2") (pintype "passive"))
      (node (ref "R8") (pin "1") (pinfunction "1_1") (pintype "passive"))
    )
    (net (code "47") (name "Net-(JP1-Pad5)") (class "Default")
      (node (ref "JP1") (pin "5") (pinfunction "5_5") (pintype "passive"))
      (node (ref "R7") (pin "2") (pinfunction "2_2") (pintype "passive"))
    )
    (net (code "48") (name "Net-(LED1-K)") (class "Default")
      (node (ref "LED1") (pin "2") (pinfunction "K_2") (pintype "passive"))
      (node (ref "R1") (pin "1") (pinfunction "1_1") (pintype "passive"))
    )
    (net (code "49") (name "Net-(LED2-K)") (class "Default")
      (node (ref "LED2") (pin "2") (pinfunction "K_2") (pintype "passive"))
      (node (ref "R2") (pin "1") (pinfunction "1_1") (pintype "passive"))
    )
    (net (code "50") (name "Net-(LED3-K)") (class "Default")
      (node (ref "LED3") (pin "2") (pinfunction "K_2") (pintype "passive"))
      (node (ref "R3") (pin "1") (pinfunction "1_1") (pintype "passive"))
    )
    (net (code "51") (name "Net-(LED4-K)") (class "Default")
      (node (ref "LED4") (pin "2") (pinfunction "K_2") (pintype "passive"))
      (node (ref "R13") (pin "1") (pinfunction "1_1") (pintype "passive"))
    )
    (net (code "52") (name "Net-(LED5-K)") (class "Default")
      (node (ref "LED5") (pin "2") (pinfunction "K_2") (pintype "passive"))
      (node (ref "R16") (pin "1") (pinfunction "1_1") (pintype "passive"))
    )
    (net (code "53") (name "Net-(U3-EN)") (class "Default")
      (node (ref "R6") (pin "2") (pinfunction "2_2") (pintype "passive"))
      (node (ref "U3") (pin "3") (pinfunction "EN_3") (pintype "input"))
    )
    (net (code "54") (name "Net-(U4-EN)") (class "Default")
      (node (ref "R9") (pin "2") (pinfunction "2_2") (pintype "passive"))
      (node (ref "U4") (pin "3") (pinfunction "EN_3") (pintype "input"))
    )
    (net (code "55") (name "unconnected-(IMU_Ex1-RST-Pad6)") (class "Default")
      (node (ref "IMU_Ex1") (pin "6") (pinfunction "RST_6") (pintype "passive"))
    )
    (net (code "56") (name "unconnected-(IMU_Ex1-Vin-Pad1)") (class "Default")
      (node (ref "IMU_Ex1") (pin "1") (pinfunction "Vin_1") (pintype "passive"))
    )
    (net (code "57") (name "unconnected-(IMU_IN1-INT-Pad8)") (class "Default")
      (node (ref "IMU_IN1") (pin "8") (pinfunction "INT_8") (pintype "passive"))
    )
    (net (code "58") (name "unconnected-(IMU_IN1-PS0-Pad10)") (class "Default")
      (node (ref "IMU_IN1") (pin "10") (pinfunction "PS0_10") (pintype "passive"))
    )
    (net (code "59") (name "unconnected-(IMU_IN1-PS1-Pad9)") (class "Default")
      (node (ref "IMU_IN1") (pin "9") (pinfunction "PS1_9") (pintype "passive"))
    )
    (net (code "60") (name "unconnected-(IMU_IN1-RST-Pad6)") (class "Default")
      (node (ref "IMU_IN1") (pin "6") (pinfunction "RST_6") (pintype "passive"))
    )
    (net (code "61") (name "unconnected-(IMU_IN1-Vin-Pad1)") (class "Default")
      (node (ref "IMU_IN1") (pin "1") (pinfunction "Vin_1") (pintype "passive"))
    )
    (net (code "62") (name "unconnected-(JP2-Pad1)") (class "Default")
      (node (ref "JP2") (pin "1") (pinfunction "1_1") (pintype "passive+no_connect"))
    )
    (net (code "63") (name "unconnected-(JP2-Pad3)") (class "Default")
      (node (ref "JP2") (pin "3") (pinfunction "3_3") (pintype "passive+no_connect"))
    )
    (net (code "64") (name "unconnected-(JP2-Pad4)") (class "Default")
      (node (ref "JP2") (pin "4") (pinfunction "4_4") (pintype "passive+no_connect"))
    )
    (net (code "65") (name "unconnected-(JP2-Pad5)") (class "Default")
      (node (ref "JP2") (pin "5") (pinfunction "5_5") (pintype "passive+no_connect"))
    )
    (net (code "66") (name "unconnected-(JP2-Pad6)") (class "Default")
      (node (ref "JP2") (pin "6") (pinfunction "6_6") (pintype "passive+no_connect"))
    )
    (net (code "67") (name "unconnected-(JP2-Pad7)") (class "Default")
      (node (ref "JP2") (pin "7") (pinfunction "7_7") (pintype "passive+no_connect"))
    )
    (net (code "68") (name "unconnected-(JP2-Pad8)") (class "Default")
      (node (ref "JP2") (pin "8") (pinfunction "8_8") (pintype "passive+no_connect"))
    )
    (net (code "69") (name "unconnected-(JP2-Pad9)") (class "Default")
      (node (ref "JP2") (pin "9") (pinfunction "9_9") (pintype "passive+no_connect"))
    )
    (net (code "70") (name "unconnected-(JP2-Pad10)") (class "Default")
      (node (ref "JP2") (pin "10") (pinfunction "10_10") (pintype "passive+no_connect"))
    )
    (net (code "71") (name "unconnected-(JP2-Pad11)") (class "Default")
      (node (ref "JP2") (pin "11") (pinfunction "11_11") (pintype "passive+no_connect"))
    )
    (net (code "72") (name "unconnected-(JP2-Pad13)") (class "Default")
      (node (ref "JP2") (pin "13") (pinfunction "13_13") (pintype "passive+no_connect"))
    )
    (net (code "73") (name "unconnected-(JP2-Pad14)") (class "Default")
      (node (ref "JP2") (pin "14") (pinfunction "14_14") (pintype "passive+no_connect"))
    )
    (net (code "74") (name "unconnected-(JP2-Pad19)") (class "Default")
      (node (ref "JP2") (pin "19") (pinfunction "19_19") (pintype "passive+no_connect"))
    )
    (net (code "75") (name "unconnected-(JP2-Pad20)") (class "Default")
      (node (ref "JP2") (pin "20") (pinfunction "20_20") (pintype "passive+no_connect"))
    )
    (net (code "76") (name "unconnected-(JP2-Pad23)") (class "Default")
      (node (ref "JP2") (pin "23") (pinfunction "23_23") (pintype "passive+no_connect"))
    )
    (net (code "77") (name "unconnected-(JP2-Pad24)") (class "Default")
      (node (ref "JP2") (pin "24") (pinfunction "24_24") (pintype "passive+no_connect"))
    )
    (net (code "78") (name "unconnected-(U1-PA0-WKUP-Pad10)") (class "Default")
      (node (ref "U1") (pin "10") (pinfunction "PA0-WKUP_10") (pintype "bidirectional+no_connect"))
    )
    (net (code "79") (name "unconnected-(U1-PA1-Pad11)") (class "Default")
      (node (ref "U1") (pin "11") (pinfunction "PA1_11") (pintype "bidirectional+no_connect"))
    )
    (net (code "80") (name "unconnected-(U1-PA8-Pad29)") (class "Default")
      (node (ref "U1") (pin "29") (pinfunction "PA8_29") (pintype "bidirectional+no_connect"))
    )
    (net (code "81") (name "unconnected-(U1-PA11{slash}USB--Pad32)") (class "Default")
      (node (ref "U1") (pin "32") (pinfunction "PA11/USB-_32") (pintype "bidirectional+no_connect"))
    )
    (net (code "82") (name "unconnected-(U1-PA12{slash}USB+-Pad33)") (class "Default")
      (node (ref "U1") (pin "33") (pinfunction "PA12/USB+_33") (pintype "bidirectional+no_connect"))
    )
    (net (code "83") (name "unconnected-(U1-PA15{slash}JTDI-Pad38)") (class "Default")
      (node (ref "U1") (pin "38") (pinfunction "PA15/JTDI_38") (pintype "bidirectional+no_connect"))
    )
    (net (code "84") (name "unconnected-(U1-PB3{slash}JTDO-Pad39)") (class "Default")
      (node (ref "U1") (pin "39") (pinfunction "PB3/JTDO_39") (pintype "bidirectional+no_connect"))
    )
    (net (code "85") (name "unconnected-(U1-PB4{slash}JNTRST-Pad40)") (class "Default")
      (node (ref "U1") (pin "40") (pinfunction "PB4/JNTRST_40") (pintype "bidirectional+no_connect"))
    )
    (net (code "86") (name "unconnected-(U1-PB5-Pad41)") (class "Default")
      (node (ref "U1") (pin "41") (pinfunction "PB5_41") (pintype "bidirectional+no_connect"))
    )
    (net (code "87") (name "unconnected-(U1-PB6-Pad42)") (class "Default")
      (node (ref "U1") (pin "42") (pinfunction "PB6_42") (pintype "bidirectional+no_connect"))
    )
    (net (code "88") (name "unconnected-(U1-PB7-Pad43)") (class "Default")
      (node (ref "U1") (pin "43") (pinfunction "PB7_43") (pintype "bidirectional+no_connect"))
    )
    (net (code "89") (name "unconnected-(U1-PB8-Pad45)") (class "Default")
      (node (ref "U1") (pin "45") (pinfunction "PB8_45") (pintype "bidirectional+no_connect"))
    )
    (net (code "90") (name "unconnected-(U1-PB10-Pad21)") (class "Default")
      (node (ref "U1") (pin "21") (pinfunction "PB10_21") (pintype "bidirectional+no_connect"))
    )
    (net (code "91") (name "unconnected-(U1-PB11-Pad22)") (class "Default")
      (node (ref "U1") (pin "22") (pinfunction "PB11_22") (pintype "bidirectional+no_connect"))
    )
    (net (code "92") (name "unconnected-(U1-PB12-Pad25)") (class "Default")
      (node (ref "U1") (pin "25") (pinfunction "PB12_25") (pintype "bidirectional+no_connect"))
    )
    (net (code "93") (name "unconnected-(U1-PB13-Pad26)") (class "Default")
      (node (ref "U1") (pin "26") (pinfunction "PB13_26") (pintype "bidirectional+no_connect"))
    )
    (net (code "94") (name "unconnected-(U1-PB14-Pad27)") (class "Default")
      (node (ref "U1") (pin "27") (pinfunction "PB14_27") (pintype "bidirectional+no_connect"))
    )
    (net (code "95") (name "unconnected-(U1-PB15-Pad28)") (class "Default")
      (node (ref "U1") (pin "28") (pinfunction "PB15_28") (pintype "bidirectional+no_connect"))
    )
    (net (code "96") (name "unconnected-(U1-VBAT-Pad1)") (class "Default")
      (node (ref "U1") (pin "1") (pinfunction "VBAT_1") (pintype "power_in+no_connect"))
    )
    (net (code "97") (name "unconnected-(U2-IN+-Pad5)") (class "Default")
      (node (ref "U2") (pin "5") (pinfunction "IN+_5") (pintype "passive"))
    )
    (net (code "98") (name "unconnected-(U2-IN--Pad6)") (class "Default")
      (node (ref "U2") (pin "6") (pinfunction "IN-_6") (pintype "passive"))
    )
    (net (code "99") (name "unconnected-(U5-GND-Pad39_1)") (class "Default")
      (node (ref "U5") (pin "39_1") (pinfunction "GND_39_1") (pintype "power_in"))
    )
    (net (code "100") (name "unconnected-(U5-GND-Pad39_2)") (class "Default")
      (node (ref "U5") (pin "39_2") (pinfunction "GND_39_2") (pintype "power_in"))
    )
    (net (code "101") (name "unconnected-(U5-GND-Pad39_3)") (class "Default")
      (node (ref "U5") (pin "39_3") (pinfunction "GND_39_3") (pintype "power_in"))
    )
    (net (code "102") (name "unconnected-(U5-GND-Pad39_4)") (class "Default")
      (node (ref "U5") (pin "39_4") (pinfunction "GND_39_4") (pintype "power_in"))
    )
    (net (code "103") (name "unconnected-(U5-GND-Pad39_5)") (class "Default")
      (node (ref "U5") (pin "39_5") (pinfunction "GND_39_5") (pintype "power_in"))
    )
    (net (code "104") (name "unconnected-(U5-GND-Pad39_6)") (class "Default")
      (node (ref "U5") (pin "39_6") (pinfunction "GND_39_6") (pintype "power_in"))
    )
    (net (code "105") (name "unconnected-(U5-GND-Pad39_7)") (class "Default")
      (node (ref "U5") (pin "39_7") (pinfunction "GND_39_7") (pintype "power_in"))
    )
    (net (code "106") (name "unconnected-(U5-GND-Pad39_8)") (class "Default")
      (node (ref "U5") (pin "39_8") (pinfunction "GND_39_8") (pintype "power_in"))
    )
    (net (code "107") (name "unconnected-(U5-GND-Pad39_9)") (class "Default")
      (node (ref "U5") (pin "39_9") (pinfunction "GND_39_9") (pintype "power_in"))
    )
    (net (code "108") (name "unconnected-(U5-IO13-Pad16)") (class "Default")
      (node (ref "U5") (pin "16") (pinfunction "IO13_16") (pintype "bidirectional+no_connect"))
    )
    (net (code "109") (name "unconnected-(U5-IO14-Pad13)") (class "Default")
      (node (ref "U5") (pin "13") (pinfunction "IO14_13") (pintype "bidirectional+no_connect"))
    )
    (net (code "110") (name "unconnected-(U5-IO15-Pad23)") (class "Default")
      (node (ref "U5") (pin "23") (pinfunction "IO15_23") (pintype "bidirectional+no_connect"))
    )
    (net (code "111") (name "unconnected-(U5-IO25-Pad10)") (class "Default")
      (node (ref "U5") (pin "10") (pinfunction "IO25_10") (pintype "bidirectional+no_connect"))
    )
    (net (code "112") (name "unconnected-(U5-IO26-Pad11)") (class "Default")
      (node (ref "U5") (pin "11") (pinfunction "IO26_11") (pintype "bidirectional+no_connect"))
    )
    (net (code "113") (name "unconnected-(U5-IO36{slash}SENSOR_VP-Pad4)") (class "Default")
      (node (ref "U5") (pin "4") (pinfunction "IO36/SENSOR_VP_4") (pintype "input+no_connect"))
    )
    (net (code "114") (name "unconnected-(U5-IO39{slash}SENSOR_VN-Pad5)") (class "Default")
      (node (ref "U5") (pin "5") (pinfunction "IO39/SENSOR_VN_5") (pintype "input+no_connect"))
    )
    (net (code "115") (name "unconnected-(U5-NC-Pad32)") (class "Default")
      (node (ref "U5") (pin "32") (pinfunction "NC_32") (pintype "passive"))
    )
    (net (code "116") (name "unconnected-(U5-SCL{slash}CLK-Pad20)") (class "Default")
      (node (ref "U5") (pin "20") (pinfunction "SCL/CLK_20") (pintype "bidirectional+no_connect"))
    )
    (net (code "117") (name "unconnected-(U5-SCS{slash}CMD-Pad19)") (class "Default")
      (node (ref "U5") (pin "19") (pinfunction "SCS/CMD_19") (pintype "bidirectional+no_connect"))
    )
    (net (code "118") (name "unconnected-(U5-SD1{slash}SD1-Pad22)") (class "Default")
      (node (ref "U5") (pin "22") (pinfunction "SD1/SD1_22") (pintype "bidirectional+no_connect"))
    )
    (net (code "119") (name "unconnected-(U5-SDO{slash}SD0-Pad21)") (class "Default")
      (node (ref "U5") (pin "21") (pinfunction "SDO/SD0_21") (pintype "bidirectional+no_connect"))
    )
    (net (code "120") (name "unconnected-(U5-SHD{slash}SD2-Pad17)") (class "Default")
      (node (ref "U5") (pin "17") (pinfunction "SHD/SD2_17") (pintype "bidirectional+no_connect"))
    )
    (net (code "121") (name "unconnected-(U5-SWP{slash}SD3-Pad18)") (class "Default")
      (node (ref "U5") (pin "18") (pinfunction "SWP/SD3_18") (pintype "bidirectional+no_connect"))
    )
  )
)
